# FPGA_QDRII.net
KiCad netlist of a schematic drawn in Altium Designer
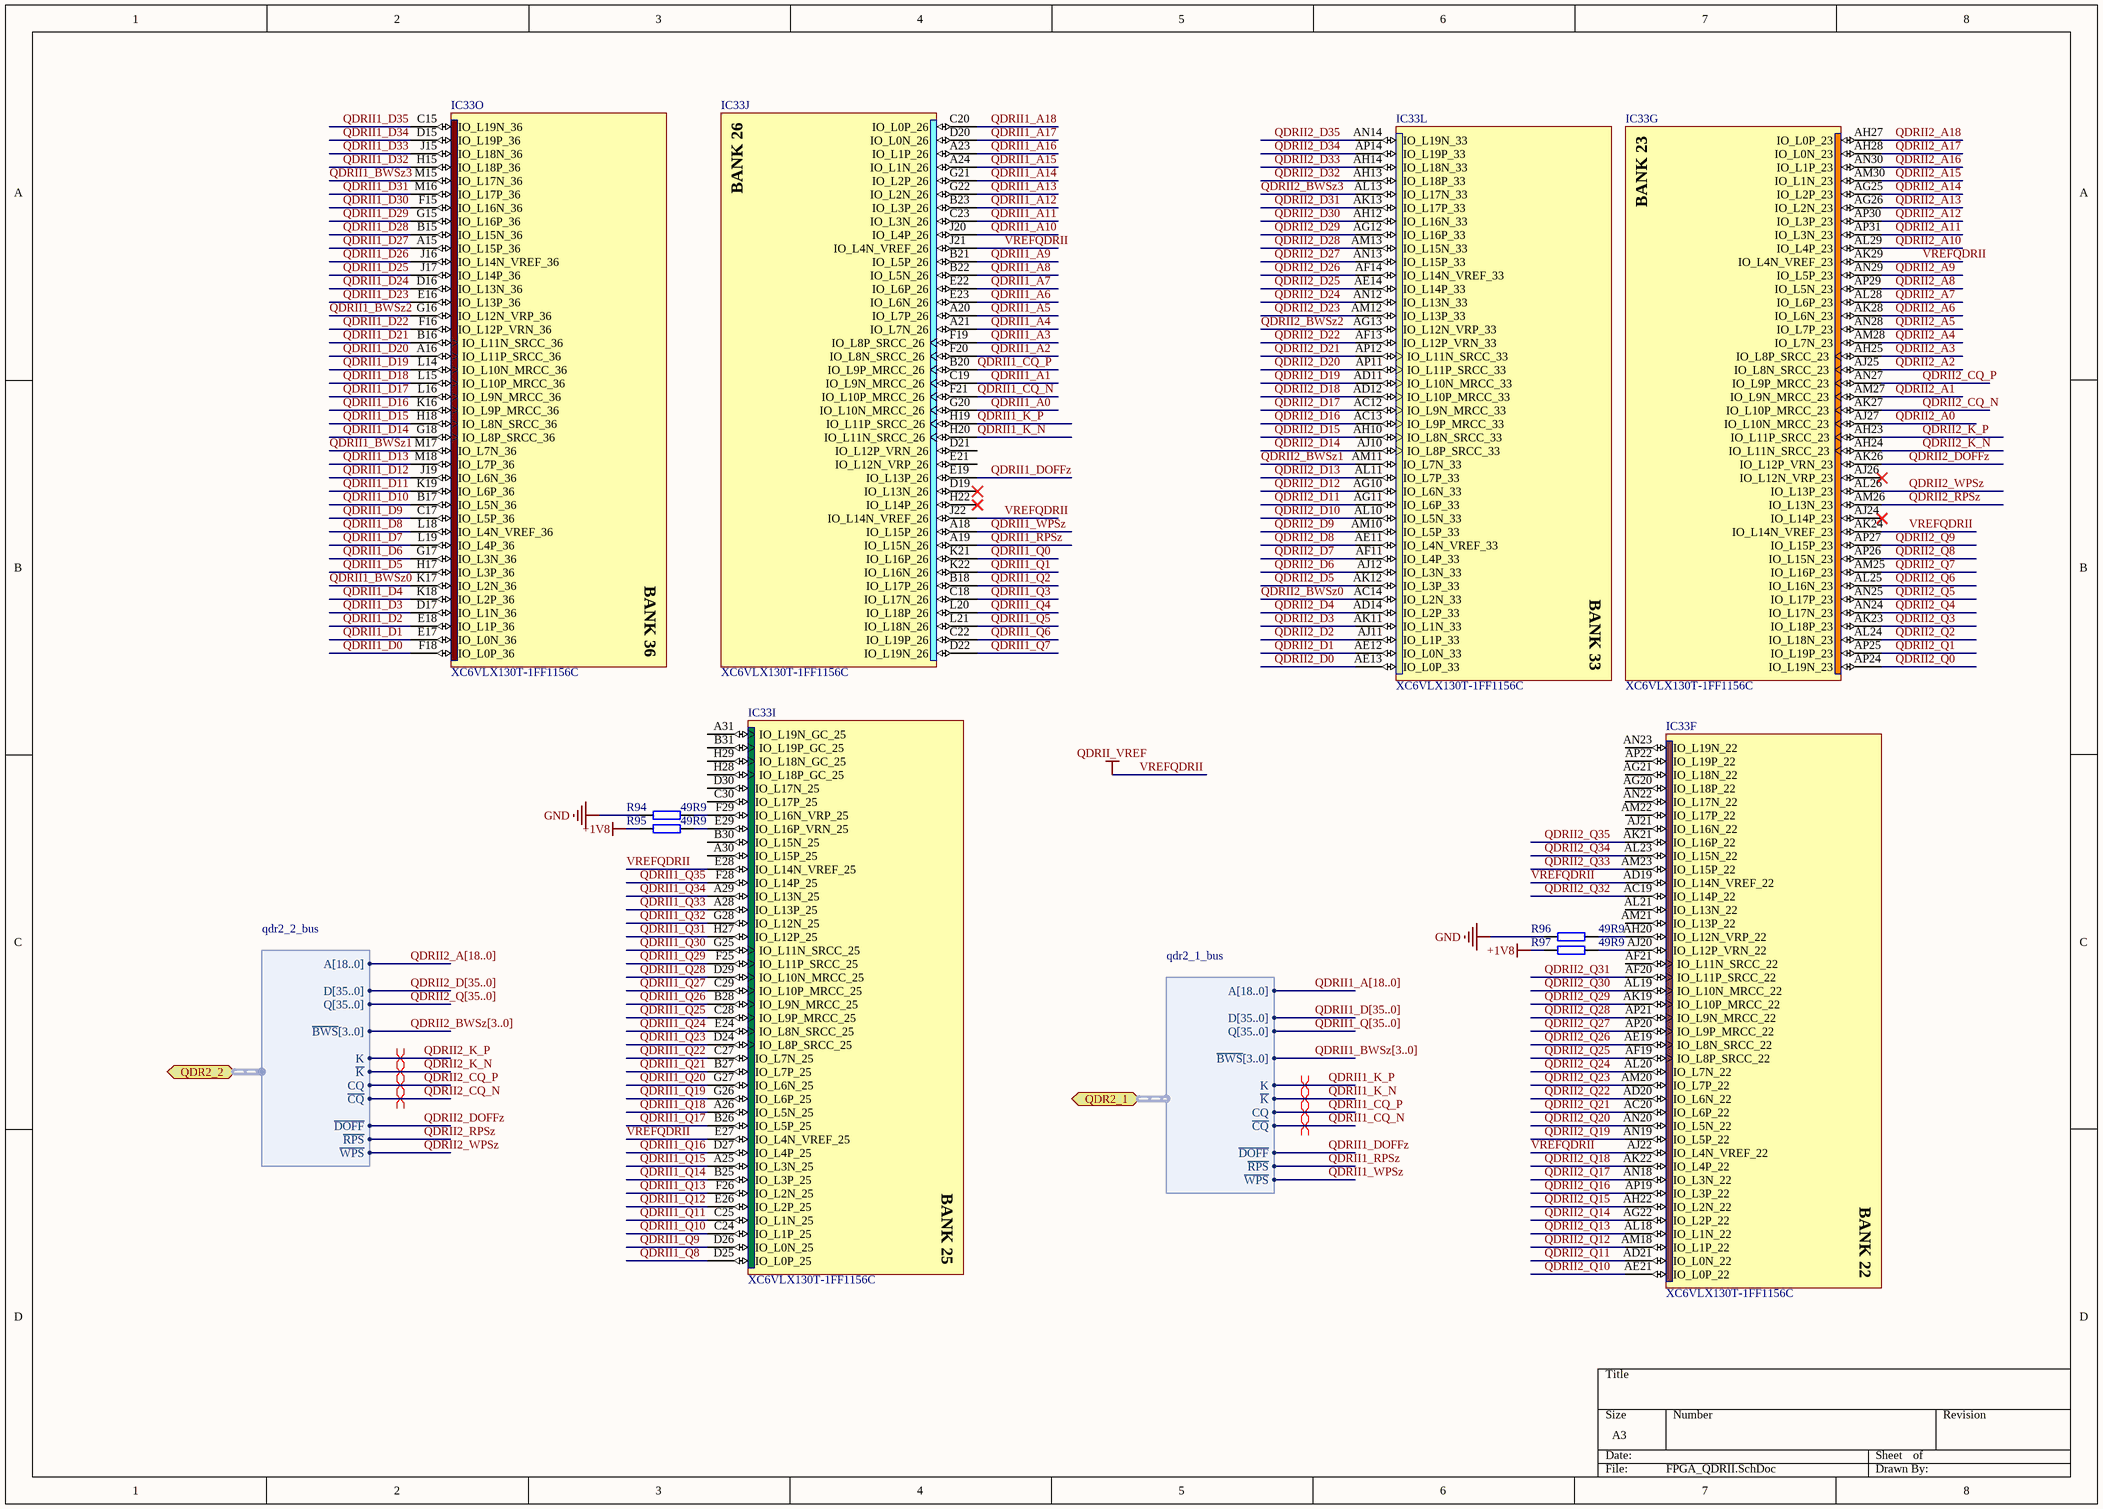
[diagram p0: FPGA_QDRII.SchDoc]

(export (version "E")
  (design (tool "Eeschema 10.0.6"))
  (components
    (comp (ref "IC33")
      (value "XC6VLX130T-1FF1156C")
      (footprint "FF1156")
      (fields (field (name "PUBLISHER") "Altium Limited"))
      (libsource (lib "Xilinx Virtex-6") (part "XC6VLX130T-1FF1156C"))
    )
    (comp (ref "R94")
      (value "49R9")
      (footprint "0402")
      (description "SMD Resistor")
      (fields (field (name "TOLERANCE") "±1%"))
      (libsource (lib "wr_switch") (part "RES_SMD"))
    )
    (comp (ref "R95")
      (value "49R9")
      (footprint "0402")
      (description "SMD Resistor")
      (fields (field (name "TOLERANCE") "±1%"))
      (libsource (lib "wr_switch") (part "RES_SMD"))
    )
    (comp (ref "R96")
      (value "49R9")
      (footprint "0402")
      (description "SMD Resistor")
      (fields (field (name "TOLERANCE") "±1%"))
      (libsource (lib "wr_switch") (part "RES_SMD"))
    )
    (comp (ref "R97")
      (value "49R9")
      (footprint "0402")
      (description "SMD Resistor")
      (fields (field (name "TOLERANCE") "±1%"))
      (libsource (lib "wr_switch") (part "RES_SMD"))
    )
  )
  (nets
    (net (code "3") (name "+1V8") (class "Default")
      (node (ref "R95") (pin "2") (pinfunction "2_2") (pintype "passive"))
      (node (ref "R97") (pin "2") (pinfunction "2_2") (pintype "passive"))
    )
    (net (code "5") (name "/QDRII1_A0") (class "Default")
      (node (ref "IC33") (pin "G20") (pinfunction "IO_L10N_MRCC_26_G20") (pintype "bidirectional"))
    )
    (net (code "6") (name "/QDRII1_A1") (class "Default")
      (node (ref "IC33") (pin "C19") (pinfunction "IO_L9N_MRCC_26_C19") (pintype "bidirectional"))
    )
    (net (code "7") (name "/QDRII1_A2") (class "Default")
      (node (ref "IC33") (pin "F20") (pinfunction "IO_L8N_SRCC_26_F20") (pintype "bidirectional"))
    )
    (net (code "8") (name "/QDRII1_A3") (class "Default")
      (node (ref "IC33") (pin "F19") (pinfunction "IO_L8P_SRCC_26_F19") (pintype "bidirectional"))
    )
    (net (code "9") (name "/QDRII1_A4") (class "Default")
      (node (ref "IC33") (pin "A21") (pinfunction "IO_L7N_26_A21") (pintype "bidirectional"))
    )
    (net (code "10") (name "/QDRII1_A5") (class "Default")
      (node (ref "IC33") (pin "A20") (pinfunction "IO_L7P_26_A20") (pintype "bidirectional"))
    )
    (net (code "11") (name "/QDRII1_A6") (class "Default")
      (node (ref "IC33") (pin "E23") (pinfunction "IO_L6N_26_E23") (pintype "bidirectional"))
    )
    (net (code "12") (name "/QDRII1_A7") (class "Default")
      (node (ref "IC33") (pin "E22") (pinfunction "IO_L6P_26_E22") (pintype "bidirectional"))
    )
    (net (code "13") (name "/QDRII1_A8") (class "Default")
      (node (ref "IC33") (pin "B22") (pinfunction "IO_L5N_26_B22") (pintype "bidirectional"))
    )
    (net (code "14") (name "/QDRII1_A9") (class "Default")
      (node (ref "IC33") (pin "B21") (pinfunction "IO_L5P_26_B21") (pintype "bidirectional"))
    )
    (net (code "15") (name "/QDRII1_A10") (class "Default")
      (node (ref "IC33") (pin "J20") (pinfunction "IO_L4P_26_J20") (pintype "bidirectional"))
    )
    (net (code "16") (name "/QDRII1_A11") (class "Default")
      (node (ref "IC33") (pin "C23") (pinfunction "IO_L3N_26_C23") (pintype "bidirectional"))
    )
    (net (code "17") (name "/QDRII1_A12") (class "Default")
      (node (ref "IC33") (pin "B23") (pinfunction "IO_L3P_26_B23") (pintype "bidirectional"))
    )
    (net (code "18") (name "/QDRII1_A13") (class "Default")
      (node (ref "IC33") (pin "G22") (pinfunction "IO_L2N_26_G22") (pintype "bidirectional"))
    )
    (net (code "19") (name "/QDRII1_A14") (class "Default")
      (node (ref "IC33") (pin "G21") (pinfunction "IO_L2P_26_G21") (pintype "bidirectional"))
    )
    (net (code "20") (name "/QDRII1_A15") (class "Default")
      (node (ref "IC33") (pin "A24") (pinfunction "IO_L1N_26_A24") (pintype "bidirectional"))
    )
    (net (code "21") (name "/QDRII1_A16") (class "Default")
      (node (ref "IC33") (pin "A23") (pinfunction "IO_L1P_26_A23") (pintype "bidirectional"))
    )
    (net (code "22") (name "/QDRII1_A17") (class "Default")
      (node (ref "IC33") (pin "D20") (pinfunction "IO_L0N_26_D20") (pintype "bidirectional"))
    )
    (net (code "23") (name "/QDRII1_A18") (class "Default")
      (node (ref "IC33") (pin "C20") (pinfunction "IO_L0P_26_C20") (pintype "bidirectional"))
    )
    (net (code "25") (name "/QDRII1_BWSz0") (class "Default")
      (node (ref "IC33") (pin "K17") (pinfunction "IO_L2N_36_K17") (pintype "bidirectional"))
    )
    (net (code "26") (name "/QDRII1_BWSz1") (class "Default")
      (node (ref "IC33") (pin "M17") (pinfunction "IO_L7N_36_M17") (pintype "bidirectional"))
    )
    (net (code "27") (name "/QDRII1_BWSz2") (class "Default")
      (node (ref "IC33") (pin "G16") (pinfunction "IO_L12N_VRP_36_G16") (pintype "bidirectional"))
    )
    (net (code "28") (name "/QDRII1_BWSz3") (class "Default")
      (node (ref "IC33") (pin "M15") (pinfunction "IO_L17N_36_M15") (pintype "bidirectional"))
    )
    (net (code "30") (name "/QDRII1_CQ_N") (class "Default")
      (node (ref "IC33") (pin "F21") (pinfunction "IO_L10P_MRCC_26_F21") (pintype "bidirectional"))
    )
    (net (code "31") (name "/QDRII1_CQ_P") (class "Default")
      (node (ref "IC33") (pin "B20") (pinfunction "IO_L9P_MRCC_26_B20") (pintype "bidirectional"))
    )
    (net (code "32") (name "/QDRII1_D0") (class "Default")
      (node (ref "IC33") (pin "F18") (pinfunction "IO_L0P_36_F18") (pintype "bidirectional"))
    )
    (net (code "33") (name "/QDRII1_D1") (class "Default")
      (node (ref "IC33") (pin "E17") (pinfunction "IO_L0N_36_E17") (pintype "bidirectional"))
    )
    (net (code "34") (name "/QDRII1_D2") (class "Default")
      (node (ref "IC33") (pin "E18") (pinfunction "IO_L1P_36_E18") (pintype "bidirectional"))
    )
    (net (code "35") (name "/QDRII1_D3") (class "Default")
      (node (ref "IC33") (pin "D17") (pinfunction "IO_L1N_36_D17") (pintype "bidirectional"))
    )
    (net (code "36") (name "/QDRII1_D4") (class "Default")
      (node (ref "IC33") (pin "K18") (pinfunction "IO_L2P_36_K18") (pintype "bidirectional"))
    )
    (net (code "37") (name "/QDRII1_D5") (class "Default")
      (node (ref "IC33") (pin "H17") (pinfunction "IO_L3P_36_H17") (pintype "bidirectional"))
    )
    (net (code "38") (name "/QDRII1_D6") (class "Default")
      (node (ref "IC33") (pin "G17") (pinfunction "IO_L3N_36_G17") (pintype "bidirectional"))
    )
    (net (code "39") (name "/QDRII1_D7") (class "Default")
      (node (ref "IC33") (pin "L19") (pinfunction "IO_L4P_36_L19") (pintype "bidirectional"))
    )
    (net (code "40") (name "/QDRII1_D8") (class "Default")
      (node (ref "IC33") (pin "L18") (pinfunction "IO_L4N_VREF_36_L18") (pintype "bidirectional"))
    )
    (net (code "41") (name "/QDRII1_D9") (class "Default")
      (node (ref "IC33") (pin "C17") (pinfunction "IO_L5P_36_C17") (pintype "bidirectional"))
    )
    (net (code "42") (name "/QDRII1_D10") (class "Default")
      (node (ref "IC33") (pin "B17") (pinfunction "IO_L5N_36_B17") (pintype "bidirectional"))
    )
    (net (code "43") (name "/QDRII1_D11") (class "Default")
      (node (ref "IC33") (pin "K19") (pinfunction "IO_L6P_36_K19") (pintype "bidirectional"))
    )
    (net (code "44") (name "/QDRII1_D12") (class "Default")
      (node (ref "IC33") (pin "J19") (pinfunction "IO_L6N_36_J19") (pintype "bidirectional"))
    )
    (net (code "45") (name "/QDRII1_D13") (class "Default")
      (node (ref "IC33") (pin "M18") (pinfunction "IO_L7P_36_M18") (pintype "bidirectional"))
    )
    (net (code "46") (name "/QDRII1_D14") (class "Default")
      (node (ref "IC33") (pin "G18") (pinfunction "IO_L8P_SRCC_36_G18") (pintype "bidirectional"))
    )
    (net (code "47") (name "/QDRII1_D15") (class "Default")
      (node (ref "IC33") (pin "H18") (pinfunction "IO_L8N_SRCC_36_H18") (pintype "bidirectional"))
    )
    (net (code "48") (name "/QDRII1_D16") (class "Default")
      (node (ref "IC33") (pin "K16") (pinfunction "IO_L9P_MRCC_36_K16") (pintype "bidirectional"))
    )
    (net (code "49") (name "/QDRII1_D17") (class "Default")
      (node (ref "IC33") (pin "L16") (pinfunction "IO_L9N_MRCC_36_L16") (pintype "bidirectional"))
    )
    (net (code "50") (name "/QDRII1_D18") (class "Default")
      (node (ref "IC33") (pin "L15") (pinfunction "IO_L10P_MRCC_36_L15") (pintype "bidirectional"))
    )
    (net (code "51") (name "/QDRII1_D19") (class "Default")
      (node (ref "IC33") (pin "L14") (pinfunction "IO_L10N_MRCC_36_L14") (pintype "bidirectional"))
    )
    (net (code "52") (name "/QDRII1_D20") (class "Default")
      (node (ref "IC33") (pin "A16") (pinfunction "IO_L11P_SRCC_36_A16") (pintype "bidirectional"))
    )
    (net (code "53") (name "/QDRII1_D21") (class "Default")
      (node (ref "IC33") (pin "B16") (pinfunction "IO_L11N_SRCC_36_B16") (pintype "bidirectional"))
    )
    (net (code "54") (name "/QDRII1_D22") (class "Default")
      (node (ref "IC33") (pin "F16") (pinfunction "IO_L12P_VRN_36_F16") (pintype "bidirectional"))
    )
    (net (code "55") (name "/QDRII1_D23") (class "Default")
      (node (ref "IC33") (pin "E16") (pinfunction "IO_L13P_36_E16") (pintype "bidirectional"))
    )
    (net (code "56") (name "/QDRII1_D24") (class "Default")
      (node (ref "IC33") (pin "D16") (pinfunction "IO_L13N_36_D16") (pintype "bidirectional"))
    )
    (net (code "57") (name "/QDRII1_D25") (class "Default")
      (node (ref "IC33") (pin "J17") (pinfunction "IO_L14P_36_J17") (pintype "bidirectional"))
    )
    (net (code "58") (name "/QDRII1_D26") (class "Default")
      (node (ref "IC33") (pin "J16") (pinfunction "IO_L14N_VREF_36_J16") (pintype "bidirectional"))
    )
    (net (code "59") (name "/QDRII1_D27") (class "Default")
      (node (ref "IC33") (pin "A15") (pinfunction "IO_L15P_36_A15") (pintype "bidirectional"))
    )
    (net (code "60") (name "/QDRII1_D28") (class "Default")
      (node (ref "IC33") (pin "B15") (pinfunction "IO_L15N_36_B15") (pintype "bidirectional"))
    )
    (net (code "61") (name "/QDRII1_D29") (class "Default")
      (node (ref "IC33") (pin "G15") (pinfunction "IO_L16P_36_G15") (pintype "bidirectional"))
    )
    (net (code "62") (name "/QDRII1_D30") (class "Default")
      (node (ref "IC33") (pin "F15") (pinfunction "IO_L16N_36_F15") (pintype "bidirectional"))
    )
    (net (code "63") (name "/QDRII1_D31") (class "Default")
      (node (ref "IC33") (pin "M16") (pinfunction "IO_L17P_36_M16") (pintype "bidirectional"))
    )
    (net (code "64") (name "/QDRII1_D32") (class "Default")
      (node (ref "IC33") (pin "H15") (pinfunction "IO_L18P_36_H15") (pintype "bidirectional"))
    )
    (net (code "65") (name "/QDRII1_D33") (class "Default")
      (node (ref "IC33") (pin "J15") (pinfunction "IO_L18N_36_J15") (pintype "bidirectional"))
    )
    (net (code "66") (name "/QDRII1_D34") (class "Default")
      (node (ref "IC33") (pin "D15") (pinfunction "IO_L19P_36_D15") (pintype "bidirectional"))
    )
    (net (code "67") (name "/QDRII1_D35") (class "Default")
      (node (ref "IC33") (pin "C15") (pinfunction "IO_L19N_36_C15") (pintype "bidirectional"))
    )
    (net (code "68") (name "/QDRII1_DOFFz") (class "Default")
      (node (ref "IC33") (pin "E19") (pinfunction "IO_L13P_26_E19") (pintype "bidirectional"))
    )
    (net (code "70") (name "/QDRII1_K_N") (class "Default")
      (node (ref "IC33") (pin "H20") (pinfunction "IO_L11N_SRCC_26_H20") (pintype "bidirectional"))
    )
    (net (code "71") (name "/QDRII1_K_P") (class "Default")
      (node (ref "IC33") (pin "H19") (pinfunction "IO_L11P_SRCC_26_H19") (pintype "bidirectional"))
    )
    (net (code "72") (name "/QDRII1_Q0") (class "Default")
      (node (ref "IC33") (pin "K21") (pinfunction "IO_L16P_26_K21") (pintype "bidirectional"))
    )
    (net (code "73") (name "/QDRII1_Q1") (class "Default")
      (node (ref "IC33") (pin "K22") (pinfunction "IO_L16N_26_K22") (pintype "bidirectional"))
    )
    (net (code "74") (name "/QDRII1_Q2") (class "Default")
      (node (ref "IC33") (pin "B18") (pinfunction "IO_L17P_26_B18") (pintype "bidirectional"))
    )
    (net (code "75") (name "/QDRII1_Q3") (class "Default")
      (node (ref "IC33") (pin "C18") (pinfunction "IO_L17N_26_C18") (pintype "bidirectional"))
    )
    (net (code "76") (name "/QDRII1_Q4") (class "Default")
      (node (ref "IC33") (pin "L20") (pinfunction "IO_L18P_26_L20") (pintype "bidirectional"))
    )
    (net (code "77") (name "/QDRII1_Q5") (class "Default")
      (node (ref "IC33") (pin "L21") (pinfunction "IO_L18N_26_L21") (pintype "bidirectional"))
    )
    (net (code "78") (name "/QDRII1_Q6") (class "Default")
      (node (ref "IC33") (pin "C22") (pinfunction "IO_L19P_26_C22") (pintype "bidirectional"))
    )
    (net (code "79") (name "/QDRII1_Q7") (class "Default")
      (node (ref "IC33") (pin "D22") (pinfunction "IO_L19N_26_D22") (pintype "bidirectional"))
    )
    (net (code "80") (name "/QDRII1_Q8") (class "Default")
      (node (ref "IC33") (pin "D25") (pinfunction "IO_L0P_25_D25") (pintype "bidirectional"))
    )
    (net (code "81") (name "/QDRII1_Q9") (class "Default")
      (node (ref "IC33") (pin "D26") (pinfunction "IO_L0N_25_D26") (pintype "bidirectional"))
    )
    (net (code "82") (name "/QDRII1_Q10") (class "Default")
      (node (ref "IC33") (pin "C24") (pinfunction "IO_L1P_25_C24") (pintype "bidirectional"))
    )
    (net (code "83") (name "/QDRII1_Q11") (class "Default")
      (node (ref "IC33") (pin "C25") (pinfunction "IO_L1N_25_C25") (pintype "bidirectional"))
    )
    (net (code "84") (name "/QDRII1_Q12") (class "Default")
      (node (ref "IC33") (pin "E26") (pinfunction "IO_L2P_25_E26") (pintype "bidirectional"))
    )
    (net (code "85") (name "/QDRII1_Q13") (class "Default")
      (node (ref "IC33") (pin "F26") (pinfunction "IO_L2N_25_F26") (pintype "bidirectional"))
    )
    (net (code "86") (name "/QDRII1_Q14") (class "Default")
      (node (ref "IC33") (pin "B25") (pinfunction "IO_L3P_25_B25") (pintype "bidirectional"))
    )
    (net (code "87") (name "/QDRII1_Q15") (class "Default")
      (node (ref "IC33") (pin "A25") (pinfunction "IO_L3N_25_A25") (pintype "bidirectional"))
    )
    (net (code "88") (name "/QDRII1_Q16") (class "Default")
      (node (ref "IC33") (pin "D27") (pinfunction "IO_L4P_25_D27") (pintype "bidirectional"))
    )
    (net (code "89") (name "/QDRII1_Q17") (class "Default")
      (node (ref "IC33") (pin "B26") (pinfunction "IO_L5P_25_B26") (pintype "bidirectional"))
    )
    (net (code "90") (name "/QDRII1_Q18") (class "Default")
      (node (ref "IC33") (pin "A26") (pinfunction "IO_L5N_25_A26") (pintype "bidirectional"))
    )
    (net (code "91") (name "/QDRII1_Q19") (class "Default")
      (node (ref "IC33") (pin "G26") (pinfunction "IO_L6P_25_G26") (pintype "bidirectional"))
    )
    (net (code "92") (name "/QDRII1_Q20") (class "Default")
      (node (ref "IC33") (pin "G27") (pinfunction "IO_L6N_25_G27") (pintype "bidirectional"))
    )
    (net (code "93") (name "/QDRII1_Q21") (class "Default")
      (node (ref "IC33") (pin "B27") (pinfunction "IO_L7P_25_B27") (pintype "bidirectional"))
    )
    (net (code "94") (name "/QDRII1_Q22") (class "Default")
      (node (ref "IC33") (pin "C27") (pinfunction "IO_L7N_25_C27") (pintype "bidirectional"))
    )
    (net (code "95") (name "/QDRII1_Q23") (class "Default")
      (node (ref "IC33") (pin "D24") (pinfunction "IO_L8P_SRCC_25_D24") (pintype "bidirectional"))
    )
    (net (code "96") (name "/QDRII1_Q24") (class "Default")
      (node (ref "IC33") (pin "E24") (pinfunction "IO_L8N_SRCC_25_E24") (pintype "bidirectional"))
    )
    (net (code "97") (name "/QDRII1_Q25") (class "Default")
      (node (ref "IC33") (pin "C28") (pinfunction "IO_L9P_MRCC_25_C28") (pintype "bidirectional"))
    )
    (net (code "98") (name "/QDRII1_Q26") (class "Default")
      (node (ref "IC33") (pin "B28") (pinfunction "IO_L9N_MRCC_25_B28") (pintype "bidirectional"))
    )
    (net (code "99") (name "/QDRII1_Q27") (class "Default")
      (node (ref "IC33") (pin "C29") (pinfunction "IO_L10P_MRCC_25_C29") (pintype "bidirectional"))
    )
    (net (code "100") (name "/QDRII1_Q28") (class "Default")
      (node (ref "IC33") (pin "D29") (pinfunction "IO_L10N_MRCC_25_D29") (pintype "bidirectional"))
    )
    (net (code "101") (name "/QDRII1_Q29") (class "Default")
      (node (ref "IC33") (pin "F25") (pinfunction "IO_L11P_SRCC_25_F25") (pintype "bidirectional"))
    )
    (net (code "102") (name "/QDRII1_Q30") (class "Default")
      (node (ref "IC33") (pin "G25") (pinfunction "IO_L11N_SRCC_25_G25") (pintype "bidirectional"))
    )
    (net (code "103") (name "/QDRII1_Q31") (class "Default")
      (node (ref "IC33") (pin "H27") (pinfunction "IO_L12P_25_H27") (pintype "bidirectional"))
    )
    (net (code "104") (name "/QDRII1_Q32") (class "Default")
      (node (ref "IC33") (pin "G28") (pinfunction "IO_L12N_25_G28") (pintype "bidirectional"))
    )
    (net (code "105") (name "/QDRII1_Q33") (class "Default")
      (node (ref "IC33") (pin "A28") (pinfunction "IO_L13P_25_A28") (pintype "bidirectional"))
    )
    (net (code "106") (name "/QDRII1_Q34") (class "Default")
      (node (ref "IC33") (pin "A29") (pinfunction "IO_L13N_25_A29") (pintype "bidirectional"))
    )
    (net (code "107") (name "/QDRII1_Q35") (class "Default")
      (node (ref "IC33") (pin "F28") (pinfunction "IO_L14P_25_F28") (pintype "bidirectional"))
    )
    (net (code "109") (name "/QDRII1_RPSz") (class "Default")
      (node (ref "IC33") (pin "A19") (pinfunction "IO_L15N_26_A19") (pintype "bidirectional"))
    )
    (net (code "110") (name "/QDRII1_WPSz") (class "Default")
      (node (ref "IC33") (pin "A18") (pinfunction "IO_L15P_26_A18") (pintype "bidirectional"))
    )
    (net (code "111") (name "/QDRII2_A0") (class "Default")
      (node (ref "IC33") (pin "AJ27") (pinfunction "IO_L10N_MRCC_23_AJ27") (pintype "bidirectional"))
    )
    (net (code "112") (name "/QDRII2_A1") (class "Default")
      (node (ref "IC33") (pin "AM27") (pinfunction "IO_L9N_MRCC_23_AM27") (pintype "bidirectional"))
    )
    (net (code "113") (name "/QDRII2_A2") (class "Default")
      (node (ref "IC33") (pin "AJ25") (pinfunction "IO_L8N_SRCC_23_AJ25") (pintype "bidirectional"))
    )
    (net (code "114") (name "/QDRII2_A3") (class "Default")
      (node (ref "IC33") (pin "AH25") (pinfunction "IO_L8P_SRCC_23_AH25") (pintype "bidirectional"))
    )
    (net (code "115") (name "/QDRII2_A4") (class "Default")
      (node (ref "IC33") (pin "AM28") (pinfunction "IO_L7N_23_AM28") (pintype "bidirectional"))
    )
    (net (code "116") (name "/QDRII2_A5") (class "Default")
      (node (ref "IC33") (pin "AN28") (pinfunction "IO_L7P_23_AN28") (pintype "bidirectional"))
    )
    (net (code "117") (name "/QDRII2_A6") (class "Default")
      (node (ref "IC33") (pin "AK28") (pinfunction "IO_L6N_23_AK28") (pintype "bidirectional"))
    )
    (net (code "118") (name "/QDRII2_A7") (class "Default")
      (node (ref "IC33") (pin "AL28") (pinfunction "IO_L6P_23_AL28") (pintype "bidirectional"))
    )
    (net (code "119") (name "/QDRII2_A8") (class "Default")
      (node (ref "IC33") (pin "AP29") (pinfunction "IO_L5N_23_AP29") (pintype "bidirectional"))
    )
    (net (code "120") (name "/QDRII2_A9") (class "Default")
      (node (ref "IC33") (pin "AN29") (pinfunction "IO_L5P_23_AN29") (pintype "bidirectional"))
    )
    (net (code "121") (name "/QDRII2_A10") (class "Default")
      (node (ref "IC33") (pin "AL29") (pinfunction "IO_L4P_23_AL29") (pintype "bidirectional"))
    )
    (net (code "122") (name "/QDRII2_A11") (class "Default")
      (node (ref "IC33") (pin "AP31") (pinfunction "IO_L3N_23_AP31") (pintype "bidirectional"))
    )
    (net (code "123") (name "/QDRII2_A12") (class "Default")
      (node (ref "IC33") (pin "AP30") (pinfunction "IO_L3P_23_AP30") (pintype "bidirectional"))
    )
    (net (code "124") (name "/QDRII2_A13") (class "Default")
      (node (ref "IC33") (pin "AG26") (pinfunction "IO_L2N_23_AG26") (pintype "bidirectional"))
    )
    (net (code "125") (name "/QDRII2_A14") (class "Default")
      (node (ref "IC33") (pin "AG25") (pinfunction "IO_L2P_23_AG25") (pintype "bidirectional"))
    )
    (net (code "126") (name "/QDRII2_A15") (class "Default")
      (node (ref "IC33") (pin "AM30") (pinfunction "IO_L1N_23_AM30") (pintype "bidirectional"))
    )
    (net (code "127") (name "/QDRII2_A16") (class "Default")
      (node (ref "IC33") (pin "AN30") (pinfunction "IO_L1P_23_AN30") (pintype "bidirectional"))
    )
    (net (code "128") (name "/QDRII2_A17") (class "Default")
      (node (ref "IC33") (pin "AH28") (pinfunction "IO_L0N_23_AH28") (pintype "bidirectional"))
    )
    (net (code "129") (name "/QDRII2_A18") (class "Default")
      (node (ref "IC33") (pin "AH27") (pinfunction "IO_L0P_23_AH27") (pintype "bidirectional"))
    )
    (net (code "131") (name "/QDRII2_BWSz0") (class "Default")
      (node (ref "IC33") (pin "AC14") (pinfunction "IO_L2N_33_AC14") (pintype "bidirectional"))
    )
    (net (code "132") (name "/QDRII2_BWSz1") (class "Default")
      (node (ref "IC33") (pin "AM11") (pinfunction "IO_L7N_33_AM11") (pintype "bidirectional"))
    )
    (net (code "133") (name "/QDRII2_BWSz2") (class "Default")
      (node (ref "IC33") (pin "AG13") (pinfunction "IO_L12N_VRP_33_AG13") (pintype "bidirectional"))
    )
    (net (code "134") (name "/QDRII2_BWSz3") (class "Default")
      (node (ref "IC33") (pin "AL13") (pinfunction "IO_L17N_33_AL13") (pintype "bidirectional"))
    )
    (net (code "135") (name "/QDRII2_CQ_N") (class "Default")
      (node (ref "IC33") (pin "AK27") (pinfunction "IO_L10P_MRCC_23_AK27") (pintype "bidirectional"))
    )
    (net (code "136") (name "/QDRII2_CQ_P") (class "Default")
      (node (ref "IC33") (pin "AN27") (pinfunction "IO_L9P_MRCC_23_AN27") (pintype "bidirectional"))
    )
    (net (code "137") (name "/QDRII2_D0") (class "Default")
      (node (ref "IC33") (pin "AE13") (pinfunction "IO_L0P_33_AE13") (pintype "bidirectional"))
    )
    (net (code "138") (name "/QDRII2_D1") (class "Default")
      (node (ref "IC33") (pin "AE12") (pinfunction "IO_L0N_33_AE12") (pintype "bidirectional"))
    )
    (net (code "139") (name "/QDRII2_D2") (class "Default")
      (node (ref "IC33") (pin "AJ11") (pinfunction "IO_L1P_33_AJ11") (pintype "bidirectional"))
    )
    (net (code "140") (name "/QDRII2_D3") (class "Default")
      (node (ref "IC33") (pin "AK11") (pinfunction "IO_L1N_33_AK11") (pintype "bidirectional"))
    )
    (net (code "141") (name "/QDRII2_D4") (class "Default")
      (node (ref "IC33") (pin "AD14") (pinfunction "IO_L2P_33_AD14") (pintype "bidirectional"))
    )
    (net (code "142") (name "/QDRII2_D5") (class "Default")
      (node (ref "IC33") (pin "AK12") (pinfunction "IO_L3P_33_AK12") (pintype "bidirectional"))
    )
    (net (code "143") (name "/QDRII2_D6") (class "Default")
      (node (ref "IC33") (pin "AJ12") (pinfunction "IO_L3N_33_AJ12") (pintype "bidirectional"))
    )
    (net (code "144") (name "/QDRII2_D7") (class "Default")
      (node (ref "IC33") (pin "AF11") (pinfunction "IO_L4P_33_AF11") (pintype "bidirectional"))
    )
    (net (code "145") (name "/QDRII2_D8") (class "Default")
      (node (ref "IC33") (pin "AE11") (pinfunction "IO_L4N_VREF_33_AE11") (pintype "bidirectional"))
    )
    (net (code "146") (name "/QDRII2_D9") (class "Default")
      (node (ref "IC33") (pin "AM10") (pinfunction "IO_L5P_33_AM10") (pintype "bidirectional"))
    )
    (net (code "147") (name "/QDRII2_D10") (class "Default")
      (node (ref "IC33") (pin "AL10") (pinfunction "IO_L5N_33_AL10") (pintype "bidirectional"))
    )
    (net (code "148") (name "/QDRII2_D11") (class "Default")
      (node (ref "IC33") (pin "AG11") (pinfunction "IO_L6P_33_AG11") (pintype "bidirectional"))
    )
    (net (code "149") (name "/QDRII2_D12") (class "Default")
      (node (ref "IC33") (pin "AG10") (pinfunction "IO_L6N_33_AG10") (pintype "bidirectional"))
    )
    (net (code "150") (name "/QDRII2_D13") (class "Default")
      (node (ref "IC33") (pin "AL11") (pinfunction "IO_L7P_33_AL11") (pintype "bidirectional"))
    )
    (net (code "151") (name "/QDRII2_D14") (class "Default")
      (node (ref "IC33") (pin "AJ10") (pinfunction "IO_L8P_SRCC_33_AJ10") (pintype "bidirectional"))
    )
    (net (code "152") (name "/QDRII2_D15") (class "Default")
      (node (ref "IC33") (pin "AH10") (pinfunction "IO_L8N_SRCC_33_AH10") (pintype "bidirectional"))
    )
    (net (code "153") (name "/QDRII2_D16") (class "Default")
      (node (ref "IC33") (pin "AC13") (pinfunction "IO_L9P_MRCC_33_AC13") (pintype "bidirectional"))
    )
    (net (code "154") (name "/QDRII2_D17") (class "Default")
      (node (ref "IC33") (pin "AC12") (pinfunction "IO_L9N_MRCC_33_AC12") (pintype "bidirectional"))
    )
    (net (code "155") (name "/QDRII2_D18") (class "Default")
      (node (ref "IC33") (pin "AD12") (pinfunction "IO_L10P_MRCC_33_AD12") (pintype "bidirectional"))
    )
    (net (code "156") (name "/QDRII2_D19") (class "Default")
      (node (ref "IC33") (pin "AD11") (pinfunction "IO_L10N_MRCC_33_AD11") (pintype "bidirectional"))
    )
    (net (code "157") (name "/QDRII2_D20") (class "Default")
      (node (ref "IC33") (pin "AP11") (pinfunction "IO_L11P_SRCC_33_AP11") (pintype "bidirectional"))
    )
    (net (code "158") (name "/QDRII2_D21") (class "Default")
      (node (ref "IC33") (pin "AP12") (pinfunction "IO_L11N_SRCC_33_AP12") (pintype "bidirectional"))
    )
    (net (code "159") (name "/QDRII2_D22") (class "Default")
      (node (ref "IC33") (pin "AF13") (pinfunction "IO_L12P_VRN_33_AF13") (pintype "bidirectional"))
    )
    (net (code "160") (name "/QDRII2_D23") (class "Default")
      (node (ref "IC33") (pin "AM12") (pinfunction "IO_L13P_33_AM12") (pintype "bidirectional"))
    )
    (net (code "161") (name "/QDRII2_D24") (class "Default")
      (node (ref "IC33") (pin "AN12") (pinfunction "IO_L13N_33_AN12") (pintype "bidirectional"))
    )
    (net (code "162") (name "/QDRII2_D25") (class "Default")
      (node (ref "IC33") (pin "AE14") (pinfunction "IO_L14P_33_AE14") (pintype "bidirectional"))
    )
    (net (code "163") (name "/QDRII2_D26") (class "Default")
      (node (ref "IC33") (pin "AF14") (pinfunction "IO_L14N_VREF_33_AF14") (pintype "bidirectional"))
    )
    (net (code "164") (name "/QDRII2_D27") (class "Default")
      (node (ref "IC33") (pin "AN13") (pinfunction "IO_L15P_33_AN13") (pintype "bidirectional"))
    )
    (net (code "165") (name "/QDRII2_D28") (class "Default")
      (node (ref "IC33") (pin "AM13") (pinfunction "IO_L15N_33_AM13") (pintype "bidirectional"))
    )
    (net (code "166") (name "/QDRII2_D29") (class "Default")
      (node (ref "IC33") (pin "AG12") (pinfunction "IO_L16P_33_AG12") (pintype "bidirectional"))
    )
    (net (code "167") (name "/QDRII2_D30") (class "Default")
      (node (ref "IC33") (pin "AH12") (pinfunction "IO_L16N_33_AH12") (pintype "bidirectional"))
    )
    (net (code "168") (name "/QDRII2_D31") (class "Default")
      (node (ref "IC33") (pin "AK13") (pinfunction "IO_L17P_33_AK13") (pintype "bidirectional"))
    )
    (net (code "169") (name "/QDRII2_D32") (class "Default")
      (node (ref "IC33") (pin "AH13") (pinfunction "IO_L18P_33_AH13") (pintype "bidirectional"))
    )
    (net (code "170") (name "/QDRII2_D33") (class "Default")
      (node (ref "IC33") (pin "AH14") (pinfunction "IO_L18N_33_AH14") (pintype "bidirectional"))
    )
    (net (code "171") (name "/QDRII2_D34") (class "Default")
      (node (ref "IC33") (pin "AP14") (pinfunction "IO_L19P_33_AP14") (pintype "bidirectional"))
    )
    (net (code "172") (name "/QDRII2_D35") (class "Default")
      (node (ref "IC33") (pin "AN14") (pinfunction "IO_L19N_33_AN14") (pintype "bidirectional"))
    )
    (net (code "173") (name "/QDRII2_DOFFz") (class "Default")
      (node (ref "IC33") (pin "AK26") (pinfunction "IO_L12P_VRN_23_AK26") (pintype "bidirectional"))
    )
    (net (code "175") (name "/QDRII2_K_N") (class "Default")
      (node (ref "IC33") (pin "AH24") (pinfunction "IO_L11N_SRCC_23_AH24") (pintype "bidirectional"))
    )
    (net (code "176") (name "/QDRII2_K_P") (class "Default")
      (node (ref "IC33") (pin "AH23") (pinfunction "IO_L11P_SRCC_23_AH23") (pintype "bidirectional"))
    )
    (net (code "177") (name "/QDRII2_Q0") (class "Default")
      (node (ref "IC33") (pin "AP24") (pinfunction "IO_L19N_23_AP24") (pintype "bidirectional"))
    )
    (net (code "178") (name "/QDRII2_Q1") (class "Default")
      (node (ref "IC33") (pin "AP25") (pinfunction "IO_L19P_23_AP25") (pintype "bidirectional"))
    )
    (net (code "179") (name "/QDRII2_Q2") (class "Default")
      (node (ref "IC33") (pin "AL24") (pinfunction "IO_L18N_23_AL24") (pintype "bidirectional"))
    )
    (net (code "180") (name "/QDRII2_Q3") (class "Default")
      (node (ref "IC33") (pin "AK23") (pinfunction "IO_L18P_23_AK23") (pintype "bidirectional"))
    )
    (net (code "181") (name "/QDRII2_Q4") (class "Default")
      (node (ref "IC33") (pin "AN24") (pinfunction "IO_L17N_23_AN24") (pintype "bidirectional"))
    )
    (net (code "182") (name "/QDRII2_Q5") (class "Default")
      (node (ref "IC33") (pin "AN25") (pinfunction "IO_L17P_23_AN25") (pintype "bidirectional"))
    )
    (net (code "183") (name "/QDRII2_Q6") (class "Default")
      (node (ref "IC33") (pin "AL25") (pinfunction "IO_L16N_23_AL25") (pintype "bidirectional"))
    )
    (net (code "184") (name "/QDRII2_Q7") (class "Default")
      (node (ref "IC33") (pin "AM25") (pinfunction "IO_L16P_23_AM25") (pintype "bidirectional"))
    )
    (net (code "185") (name "/QDRII2_Q8") (class "Default")
      (node (ref "IC33") (pin "AP26") (pinfunction "IO_L15N_23_AP26") (pintype "bidirectional"))
    )
    (net (code "186") (name "/QDRII2_Q9") (class "Default")
      (node (ref "IC33") (pin "AP27") (pinfunction "IO_L15P_23_AP27") (pintype "bidirectional"))
    )
    (net (code "187") (name "/QDRII2_Q10") (class "Default")
      (node (ref "IC33") (pin "AE21") (pinfunction "IO_L0P_22_AE21") (pintype "bidirectional"))
    )
    (net (code "188") (name "/QDRII2_Q11") (class "Default")
      (node (ref "IC33") (pin "AD21") (pinfunction "IO_L0N_22_AD21") (pintype "bidirectional"))
    )
    (net (code "189") (name "/QDRII2_Q12") (class "Default")
      (node (ref "IC33") (pin "AM18") (pinfunction "IO_L1P_22_AM18") (pintype "bidirectional"))
    )
    (net (code "190") (name "/QDRII2_Q13") (class "Default")
      (node (ref "IC33") (pin "AL18") (pinfunction "IO_L1N_22_AL18") (pintype "bidirectional"))
    )
    (net (code "191") (name "/QDRII2_Q14") (class "Default")
      (node (ref "IC33") (pin "AG22") (pinfunction "IO_L2P_22_AG22") (pintype "bidirectional"))
    )
    (net (code "192") (name "/QDRII2_Q15") (class "Default")
      (node (ref "IC33") (pin "AH22") (pinfunction "IO_L2N_22_AH22") (pintype "bidirectional"))
    )
    (net (code "193") (name "/QDRII2_Q16") (class "Default")
      (node (ref "IC33") (pin "AP19") (pinfunction "IO_L3P_22_AP19") (pintype "bidirectional"))
    )
    (net (code "194") (name "/QDRII2_Q17") (class "Default")
      (node (ref "IC33") (pin "AN18") (pinfunction "IO_L3N_22_AN18") (pintype "bidirectional"))
    )
    (net (code "195") (name "/QDRII2_Q18") (class "Default")
      (node (ref "IC33") (pin "AK22") (pinfunction "IO_L4P_22_AK22") (pintype "bidirectional"))
    )
    (net (code "196") (name "/QDRII2_Q19") (class "Default")
      (node (ref "IC33") (pin "AN19") (pinfunction "IO_L5P_22_AN19") (pintype "bidirectional"))
    )
    (net (code "197") (name "/QDRII2_Q20") (class "Default")
      (node (ref "IC33") (pin "AN20") (pinfunction "IO_L5N_22_AN20") (pintype "bidirectional"))
    )
    (net (code "198") (name "/QDRII2_Q21") (class "Default")
      (node (ref "IC33") (pin "AC20") (pinfunction "IO_L6P_22_AC20") (pintype "bidirectional"))
    )
    (net (code "199") (name "/QDRII2_Q22") (class "Default")
      (node (ref "IC33") (pin "AD20") (pinfunction "IO_L6N_22_AD20") (pintype "bidirectional"))
    )
    (net (code "200") (name "/QDRII2_Q23") (class "Default")
      (node (ref "IC33") (pin "AM20") (pinfunction "IO_L7P_22_AM20") (pintype "bidirectional"))
    )
    (net (code "201") (name "/QDRII2_Q24") (class "Default")
      (node (ref "IC33") (pin "AL20") (pinfunction "IO_L7N_22_AL20") (pintype "bidirectional"))
    )
    (net (code "202") (name "/QDRII2_Q25") (class "Default")
      (node (ref "IC33") (pin "AF19") (pinfunction "IO_L8P_SRCC_22_AF19") (pintype "bidirectional"))
    )
    (net (code "203") (name "/QDRII2_Q26") (class "Default")
      (node (ref "IC33") (pin "AE19") (pinfunction "IO_L8N_SRCC_22_AE19") (pintype "bidirectional"))
    )
    (net (code "204") (name "/QDRII2_Q27") (class "Default")
      (node (ref "IC33") (pin "AP20") (pinfunction "IO_L9P_MRCC_22_AP20") (pintype "bidirectional"))
    )
    (net (code "205") (name "/QDRII2_Q28") (class "Default")
      (node (ref "IC33") (pin "AP21") (pinfunction "IO_L9N_MRCC_22_AP21") (pintype "bidirectional"))
    )
    (net (code "206") (name "/QDRII2_Q29") (class "Default")
      (node (ref "IC33") (pin "AK19") (pinfunction "IO_L10P_MRCC_22_AK19") (pintype "bidirectional"))
    )
    (net (code "207") (name "/QDRII2_Q30") (class "Default")
      (node (ref "IC33") (pin "AL19") (pinfunction "IO_L10N_MRCC_22_AL19") (pintype "bidirectional"))
    )
    (net (code "208") (name "/QDRII2_Q31") (class "Default")
      (node (ref "IC33") (pin "AF20") (pinfunction "IO_L11P_SRCC_22_AF20") (pintype "bidirectional"))
    )
    (net (code "209") (name "/QDRII2_Q32") (class "Default")
      (node (ref "IC33") (pin "AC19") (pinfunction "IO_L14P_22_AC19") (pintype "bidirectional"))
    )
    (net (code "210") (name "/QDRII2_Q33") (class "Default")
      (node (ref "IC33") (pin "AM23") (pinfunction "IO_L15P_22_AM23") (pintype "bidirectional"))
    )
    (net (code "211") (name "/QDRII2_Q34") (class "Default")
      (node (ref "IC33") (pin "AL23") (pinfunction "IO_L15N_22_AL23") (pintype "bidirectional"))
    )
    (net (code "212") (name "/QDRII2_Q35") (class "Default")
      (node (ref "IC33") (pin "AK21") (pinfunction "IO_L16P_22_AK21") (pintype "bidirectional"))
    )
    (net (code "214") (name "/QDRII2_RPSz") (class "Default")
      (node (ref "IC33") (pin "AM26") (pinfunction "IO_L13N_23_AM26") (pintype "bidirectional"))
    )
    (net (code "215") (name "/QDRII2_WPSz") (class "Default")
      (node (ref "IC33") (pin "AL26") (pinfunction "IO_L13P_23_AL26") (pintype "bidirectional"))
    )
    (net (code "218") (name "GND") (class "Default")
      (node (ref "R94") (pin "2") (pinfunction "2_2") (pintype "passive"))
      (node (ref "R96") (pin "2") (pinfunction "2_2") (pintype "passive"))
    )
    (net (code "219") (name "Net-(IC33F-IO_L12N_VRP_22)") (class "Default")
      (node (ref "IC33") (pin "AH20") (pinfunction "IO_L12N_VRP_22_AH20") (pintype "bidirectional"))
      (node (ref "R96") (pin "1") (pinfunction "1_1") (pintype "passive"))
    )
    (net (code "220") (name "Net-(IC33F-IO_L12P_VRN_22)") (class "Default")
      (node (ref "IC33") (pin "AJ20") (pinfunction "IO_L12P_VRN_22_AJ20") (pintype "bidirectional"))
      (node (ref "R97") (pin "1") (pinfunction "1_1") (pintype "passive"))
    )
    (net (code "221") (name "Net-(IC33I-IO_L16N_VRP_25)") (class "Default")
      (node (ref "IC33") (pin "F29") (pinfunction "IO_L16N_VRP_25_F29") (pintype "bidirectional"))
      (node (ref "R94") (pin "1") (pinfunction "1_1") (pintype "passive"))
    )
    (net (code "222") (name "Net-(IC33I-IO_L16P_VRN_25)") (class "Default")
      (node (ref "IC33") (pin "E29") (pinfunction "IO_L16P_VRN_25_E29") (pintype "bidirectional"))
      (node (ref "R95") (pin "1") (pinfunction "1_1") (pintype "passive"))
    )
    (net (code "223") (name "QDRII_VREF") (class "Default")
      (node (ref "IC33") (pin "AD19") (pinfunction "IO_L14N_VREF_22_AD19") (pintype "bidirectional"))
      (node (ref "IC33") (pin "AJ22") (pinfunction "IO_L4N_VREF_22_AJ22") (pintype "bidirectional"))
      (node (ref "IC33") (pin "AK24") (pinfunction "IO_L14N_VREF_23_AK24") (pintype "bidirectional"))
      (node (ref "IC33") (pin "AK29") (pinfunction "IO_L4N_VREF_23_AK29") (pintype "bidirectional"))
      (node (ref "IC33") (pin "E27") (pinfunction "IO_L4N_VREF_25_E27") (pintype "bidirectional"))
      (node (ref "IC33") (pin "E28") (pinfunction "IO_L14N_VREF_25_E28") (pintype "bidirectional"))
      (node (ref "IC33") (pin "J21") (pinfunction "IO_L4N_VREF_26_J21") (pintype "bidirectional"))
      (node (ref "IC33") (pin "J22") (pinfunction "IO_L14N_VREF_26_J22") (pintype "bidirectional"))
    )
    (net (code "224") (name "unconnected-(IC33F-IO_L11N_SRCC_22-PadAF21)") (class "Default")
      (node (ref "IC33") (pin "AF21") (pinfunction "IO_L11N_SRCC_22_AF21") (pintype "bidirectional"))
    )
    (net (code "225") (name "unconnected-(IC33F-IO_L13N_22-PadAL21)") (class "Default")
      (node (ref "IC33") (pin "AL21") (pinfunction "IO_L13N_22_AL21") (pintype "bidirectional"))
    )
    (net (code "226") (name "unconnected-(IC33F-IO_L13P_22-PadAM21)") (class "Default")
      (node (ref "IC33") (pin "AM21") (pinfunction "IO_L13P_22_AM21") (pintype "bidirectional"))
    )
    (net (code "227") (name "unconnected-(IC33F-IO_L16N_22-PadAJ21)") (class "Default")
      (node (ref "IC33") (pin "AJ21") (pinfunction "IO_L16N_22_AJ21") (pintype "bidirectional"))
    )
    (net (code "228") (name "unconnected-(IC33F-IO_L17N_22-PadAN22)") (class "Default")
      (node (ref "IC33") (pin "AN22") (pinfunction "IO_L17N_22_AN22") (pintype "bidirectional"))
    )
    (net (code "229") (name "unconnected-(IC33F-IO_L17P_22-PadAM22)") (class "Default")
      (node (ref "IC33") (pin "AM22") (pinfunction "IO_L17P_22_AM22") (pintype "bidirectional"))
    )
    (net (code "230") (name "unconnected-(IC33F-IO_L18N_22-PadAG21)") (class "Default")
      (node (ref "IC33") (pin "AG21") (pinfunction "IO_L18N_22_AG21") (pintype "bidirectional"))
    )
    (net (code "231") (name "unconnected-(IC33F-IO_L18P_22-PadAG20)") (class "Default")
      (node (ref "IC33") (pin "AG20") (pinfunction "IO_L18P_22_AG20") (pintype "bidirectional"))
    )
    (net (code "232") (name "unconnected-(IC33F-IO_L19N_22-PadAN23)") (class "Default")
      (node (ref "IC33") (pin "AN23") (pinfunction "IO_L19N_22_AN23") (pintype "bidirectional"))
    )
    (net (code "233") (name "unconnected-(IC33F-IO_L19P_22-PadAP22)") (class "Default")
      (node (ref "IC33") (pin "AP22") (pinfunction "IO_L19P_22_AP22") (pintype "bidirectional"))
    )
    (net (code "234") (name "unconnected-(IC33G-IO_L12N_VRP_23-PadAJ26)") (class "Default")
      (node (ref "IC33") (pin "AJ26") (pinfunction "IO_L12N_VRP_23_AJ26") (pintype "bidirectional+no_connect"))
    )
    (net (code "235") (name "unconnected-(IC33G-IO_L14P_23-PadAJ24)") (class "Default")
      (node (ref "IC33") (pin "AJ24") (pinfunction "IO_L14P_23_AJ24") (pintype "bidirectional+no_connect"))
    )
    (net (code "236") (name "unconnected-(IC33I-IO_L15N_25-PadB30)") (class "Default")
      (node (ref "IC33") (pin "B30") (pinfunction "IO_L15N_25_B30") (pintype "bidirectional"))
    )
    (net (code "237") (name "unconnected-(IC33I-IO_L15P_25-PadA30)") (class "Default")
      (node (ref "IC33") (pin "A30") (pinfunction "IO_L15P_25_A30") (pintype "bidirectional"))
    )
    (net (code "238") (name "unconnected-(IC33I-IO_L17N_25-PadD30)") (class "Default")
      (node (ref "IC33") (pin "D30") (pinfunction "IO_L17N_25_D30") (pintype "bidirectional"))
    )
    (net (code "239") (name "unconnected-(IC33I-IO_L17P_25-PadC30)") (class "Default")
      (node (ref "IC33") (pin "C30") (pinfunction "IO_L17P_25_C30") (pintype "bidirectional"))
    )
    (net (code "240") (name "unconnected-(IC33I-IO_L18N_GC_25-PadH29)") (class "Default")
      (node (ref "IC33") (pin "H29") (pinfunction "IO_L18N_GC_25_H29") (pintype "bidirectional"))
    )
    (net (code "241") (name "unconnected-(IC33I-IO_L18P_GC_25-PadH28)") (class "Default")
      (node (ref "IC33") (pin "H28") (pinfunction "IO_L18P_GC_25_H28") (pintype "bidirectional"))
    )
    (net (code "242") (name "unconnected-(IC33I-IO_L19N_GC_25-PadA31)") (class "Default")
      (node (ref "IC33") (pin "A31") (pinfunction "IO_L19N_GC_25_A31") (pintype "bidirectional"))
    )
    (net (code "243") (name "unconnected-(IC33I-IO_L19P_GC_25-PadB31)") (class "Default")
      (node (ref "IC33") (pin "B31") (pinfunction "IO_L19P_GC_25_B31") (pintype "bidirectional"))
    )
    (net (code "244") (name "unconnected-(IC33J-IO_L12N_VRP_26-PadE21)") (class "Default")
      (node (ref "IC33") (pin "E21") (pinfunction "IO_L12N_VRP_26_E21") (pintype "bidirectional"))
    )
    (net (code "245") (name "unconnected-(IC33J-IO_L12P_VRN_26-PadD21)") (class "Default")
      (node (ref "IC33") (pin "D21") (pinfunction "IO_L12P_VRN_26_D21") (pintype "bidirectional"))
    )
    (net (code "246") (name "unconnected-(IC33J-IO_L13N_26-PadD19)") (class "Default")
      (node (ref "IC33") (pin "D19") (pinfunction "IO_L13N_26_D19") (pintype "bidirectional+no_connect"))
    )
    (net (code "247") (name "unconnected-(IC33J-IO_L14P_26-PadH22)") (class "Default")
      (node (ref "IC33") (pin "H22") (pinfunction "IO_L14P_26_H22") (pintype "bidirectional+no_connect"))
    )
  )
)
